# PS_GTR.net
KiCad netlist of a schematic drawn in Altium Designer
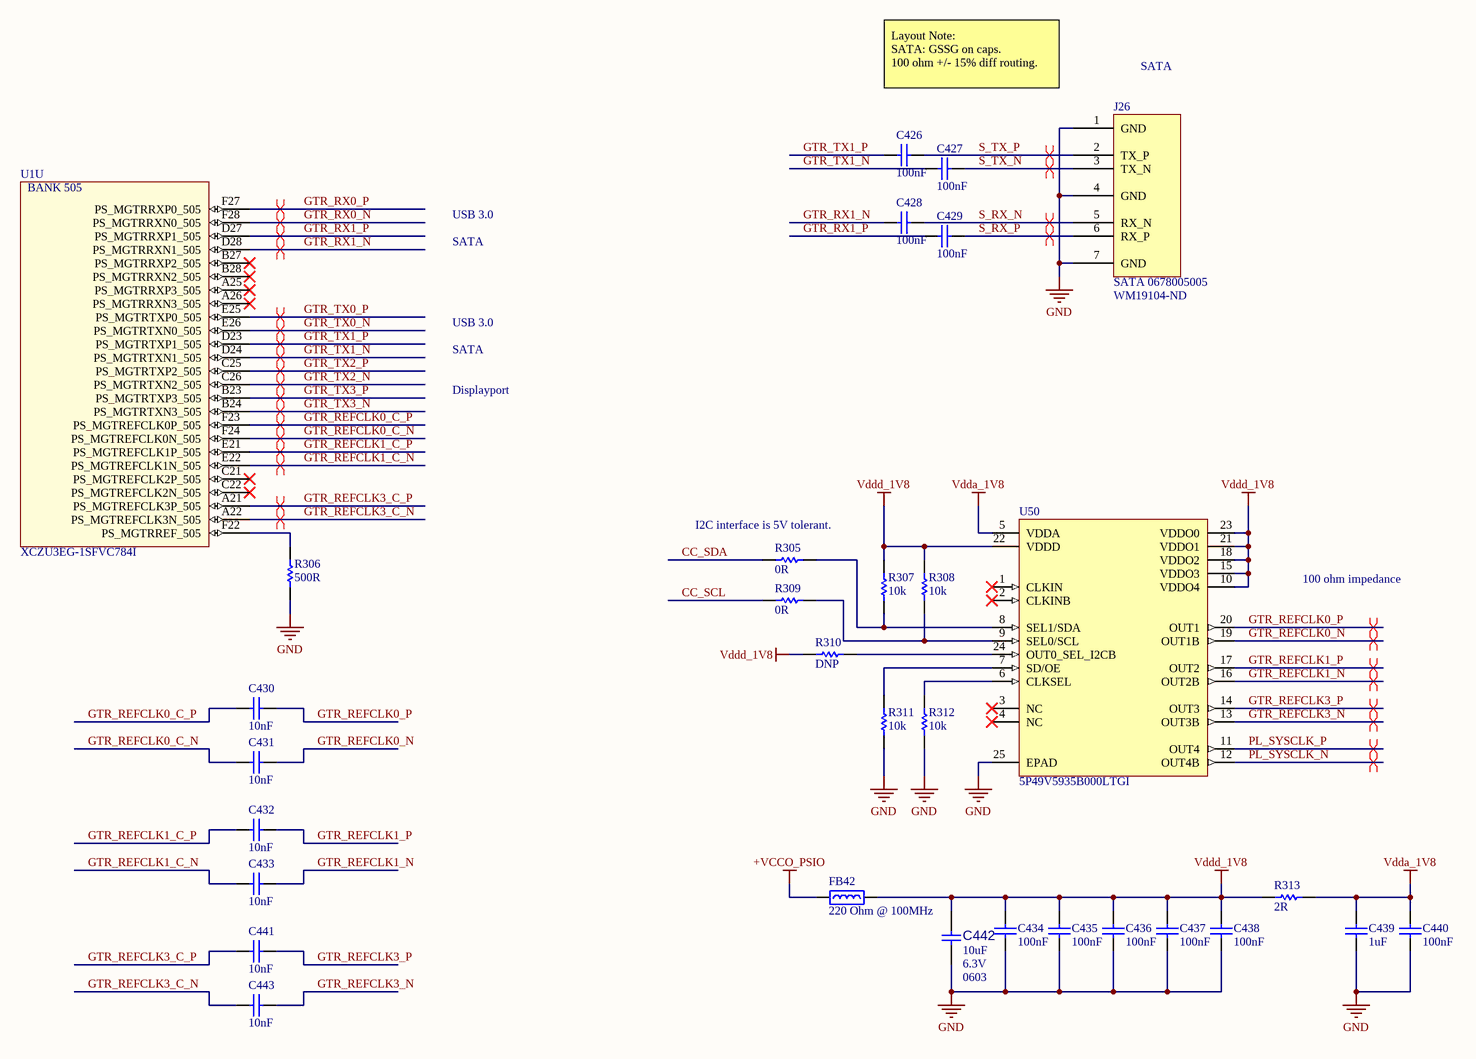
[diagram p0: PS_GTR.SchDoc]

(export (version "E")
  (design (tool "Eeschema 10.0.6"))
  (components
    (comp (ref "C426")
      (value "100nF")
      (footprint "CAPC1005L_0402")
      (description "CAP CER 0.1UF 25V X7R 0402")
      (fields (field (name "VOLTAGE") "25V") (field (name "TOLERANCE") "10%"))
      (libsource (lib "Ultrascale_SchLib") (part "CAPCER0402X7R100N25V_10T"))
    )
    (comp (ref "C427")
      (value "100nF")
      (footprint "CAPC1005L_0402")
      (description "CAP CER 0.1UF 25V X7R 0402")
      (fields (field (name "VOLTAGE") "25V") (field (name "TOLERANCE") "10%"))
      (libsource (lib "Ultrascale_SchLib") (part "CAPCER0402X7R100N25V_10T"))
    )
    (comp (ref "C428")
      (value "100nF")
      (footprint "CAPC1005L_0402")
      (description "CAP CER 0.1UF 25V X7R 0402")
      (fields (field (name "VOLTAGE") "25V") (field (name "TOLERANCE") "10%"))
      (libsource (lib "Ultrascale_SchLib") (part "CAPCER0402X7R100N25V_10T"))
    )
    (comp (ref "C429")
      (value "100nF")
      (footprint "CAPC1005L_0402")
      (description "CAP CER 0.1UF 25V X7R 0402")
      (fields (field (name "VOLTAGE") "25V") (field (name "TOLERANCE") "10%"))
      (libsource (lib "Ultrascale_SchLib") (part "CAPCER0402X7R100N25V_10T"))
    )
    (comp (ref "C430")
      (value "10nF")
      (footprint "CAPC1005L_0402")
      (description "CAP CER 10000PF (10NF) 50V X7R 0402")
      (fields (field (name "VOLTAGE") "50V") (field (name "TOLERANCE") "10%"))
      (libsource (lib "Ultrascale_SchLib") (part "CAPCER0402X7R10N50V_10T"))
    )
    (comp (ref "C431")
      (value "10nF")
      (footprint "CAPC1005L_0402")
      (description "CAP CER 10000PF (10NF) 50V X7R 0402")
      (fields (field (name "VOLTAGE") "50V") (field (name "TOLERANCE") "10%"))
      (libsource (lib "Ultrascale_SchLib") (part "CAPCER0402X7R10N50V_10T"))
    )
    (comp (ref "C432")
      (value "10nF")
      (footprint "CAPC1005L_0402")
      (description "CAP CER 10000PF (10NF) 50V X7R 0402")
      (fields (field (name "VOLTAGE") "50V") (field (name "TOLERANCE") "10%"))
      (libsource (lib "Ultrascale_SchLib") (part "CAPCER0402X7R10N50V_10T"))
    )
    (comp (ref "C433")
      (value "10nF")
      (footprint "CAPC1005L_0402")
      (description "CAP CER 10000PF (10NF) 50V X7R 0402")
      (fields (field (name "VOLTAGE") "50V") (field (name "TOLERANCE") "10%"))
      (libsource (lib "Ultrascale_SchLib") (part "CAPCER0402X7R10N50V_10T"))
    )
    (comp (ref "C434")
      (value "100nF")
      (footprint "CAPC1005L_0402")
      (description "CAP CER 0.1UF 25V X7R 0402")
      (fields (field (name "VOLTAGE") "25V") (field (name "TOLERANCE") "10%"))
      (libsource (lib "Ultrascale_SchLib") (part "CAPCER0402X7R100N25V_10T"))
    )
    (comp (ref "C435")
      (value "100nF")
      (footprint "CAPC1005L_0402")
      (description "CAP CER 0.1UF 25V X7R 0402")
      (fields (field (name "VOLTAGE") "25V") (field (name "TOLERANCE") "10%"))
      (libsource (lib "Ultrascale_SchLib") (part "CAPCER0402X7R100N25V_10T"))
    )
    (comp (ref "C436")
      (value "100nF")
      (footprint "CAPC1005L_0402")
      (description "CAP CER 0.1UF 25V X7R 0402")
      (fields (field (name "VOLTAGE") "25V") (field (name "TOLERANCE") "10%"))
      (libsource (lib "Ultrascale_SchLib") (part "CAPCER0402X7R100N25V_10T"))
    )
    (comp (ref "C437")
      (value "100nF")
      (footprint "CAPC1005L_0402")
      (description "CAP CER 0.1UF 25V X7R 0402")
      (fields (field (name "VOLTAGE") "25V") (field (name "TOLERANCE") "10%"))
      (libsource (lib "Ultrascale_SchLib") (part "CAPCER0402X7R100N25V_10T"))
    )
    (comp (ref "C438")
      (value "100nF")
      (footprint "CAPC1005L_0402")
      (description "CAP CER 0.1UF 25V X7R 0402")
      (fields (field (name "VOLTAGE") "25V") (field (name "TOLERANCE") "10%"))
      (libsource (lib "Ultrascale_SchLib") (part "CAPCER0402X7R100N25V_10T"))
    )
    (comp (ref "C439")
      (value "1uF")
      (footprint "CAPC1005L_0402")
      (description "CAP CER 1UF 16V X5R 0402")
      (fields (field (name "VOLTAGE") "16V") (field (name "TOLERANCE") "20%"))
      (libsource (lib "Ultrascale_SchLib") (part "CAPCER0402X5R1U16V_20T"))
    )
    (comp (ref "C440")
      (value "100nF")
      (footprint "CAPC1005L_0402")
      (description "CAP CER 0.1UF 25V X7R 0402")
      (fields (field (name "VOLTAGE") "25V") (field (name "TOLERANCE") "10%"))
      (libsource (lib "Ultrascale_SchLib") (part "CAPCER0402X7R100N25V_10T"))
    )
    (comp (ref "C441")
      (value "10nF")
      (footprint "CAPC1005L_0402")
      (description "CAP CER 10000PF (10NF) 50V X7R 0402")
      (fields (field (name "VOLTAGE") "50V") (field (name "TOLERANCE") "10%"))
      (libsource (lib "Ultrascale_SchLib") (part "CAPCER0402X7R10N50V_10T"))
    )
    (comp (ref "C442")
      (value "10uF")
      (footprint "Ultrascale_PcbLib:CAP_C_0603")
      (description "Capacitor")
      (fields
        (field (name "VOLTAGE") "6.3V")
        (field (name "PACKAGE") "0603")
        (field (name "TOLERANCE") "20%")
        (field (name "Comment") "Capacitor NP")
      )
      (libsource (lib "Ultrascale_SchLib") (part "Capacitor NP"))
    )
    (comp (ref "C443")
      (value "10nF")
      (footprint "CAPC1005L_0402")
      (description "CAP CER 10000PF (10NF) 50V X7R 0402")
      (fields (field (name "VOLTAGE") "50V") (field (name "TOLERANCE") "10%"))
      (libsource (lib "Ultrascale_SchLib") (part "CAPCER0402X7R10N50V_10T"))
    )
    (comp (ref "FB42")
      (value "BEAD0603_220_2A5_40M")
      (footprint "INDC1608N_0603")
      (description "FERRITE BEAD 220 OHM 0603 1LN")
      (fields (field (name "IMPEDANCE @ FREQUENCY") "220 Ohm @ 100MHz"))
      (libsource (lib "Ultrascale_SchLib") (part "BEAD0603_220_2A5_40M"))
    )
    (comp (ref "J26")
      (value "SATA 0678005005")
      (footprint "SATA HEADER")
      (description "CONN HEADER 7POS VERT SMD 15GOLD")
      (fields
        (field (name "DIGI-KEY PART NUMBER") "WM19104-ND")
        (field (name "MANUFACTURER") "Molex, LLC")
        (field (name "SUPPLIER PART NUMBER 1") "WM19104-ND")
      )
      (libsource (lib "Ultrascale_SchLib") (part "SATA 0678005005"))
    )
    (comp (ref "R305")
      (value "0R")
      (footprint "RESC1005L_0402")
      (description "RES SMD 0 OHM JUMPER 1/10W 0402")
      (fields (field (name "POWER") "1/10W") (field (name "Comment") "RES0402_0R_0W1"))
      (libsource (lib "Ultrascale_SchLib") (part "RES0402_0R_0W1"))
    )
    (comp (ref "R306")
      (value "500R")
      (footprint "RESC1005L_0402")
      (description "RES SMD 500 OHM 0.1% 1/20W 0402")
      (fields (field (name "POWER") "1/10W") (field (name "TOLERANCE") "0.1%"))
      (libsource (lib "Ultrascale_SchLib") (part "RES0402_500R_0W05_01T"))
    )
    (comp (ref "R307")
      (value "10k")
      (footprint "RESC1005L_0402")
      (description "RES SMD 10K OHM 0.5% 1/16W 0402")
      (fields (field (name "POWER") "1/16W") (field (name "TOLERANCE") "0.5%"))
      (libsource (lib "Ultrascale_SchLib") (part "RES0402_10K_0W1_05T"))
    )
    (comp (ref "R308")
      (value "10k")
      (footprint "RESC1005L_0402")
      (description "RES SMD 10K OHM 0.5% 1/16W 0402")
      (fields (field (name "POWER") "1/16W") (field (name "TOLERANCE") "0.5%"))
      (libsource (lib "Ultrascale_SchLib") (part "RES0402_10K_0W1_05T"))
    )
    (comp (ref "R309")
      (value "0R")
      (footprint "RESC1005L_0402")
      (description "RES SMD 0 OHM JUMPER 1/10W 0402")
      (fields (field (name "POWER") "1/10W") (field (name "Comment") "RES0402_0R_0W1"))
      (libsource (lib "Ultrascale_SchLib") (part "RES0402_0R_0W1"))
    )
    (comp (ref "R310")
      (value "DNP")
      (footprint "RESC1005L_0402")
      (description "RES SMD 0402 Footprint")
      (fields (field (name "Comment") "RES0402"))
      (libsource (lib "Ultrascale_SchLib") (part "RES0402"))
    )
    (comp (ref "R311")
      (value "10k")
      (footprint "RESC1005L_0402")
      (description "RES SMD 10K OHM 0.5% 1/16W 0402")
      (fields (field (name "POWER") "1/16W") (field (name "TOLERANCE") "0.5%"))
      (libsource (lib "Ultrascale_SchLib") (part "RES0402_10K_0W1_05T"))
    )
    (comp (ref "R312")
      (value "10k")
      (footprint "RESC1005L_0402")
      (description "RES SMD 10K OHM 0.5% 1/16W 0402")
      (fields (field (name "POWER") "1/16W") (field (name "TOLERANCE") "0.5%"))
      (libsource (lib "Ultrascale_SchLib") (part "RES0402_10K_0W1_05T"))
    )
    (comp (ref "R313")
      (value "2R")
      (footprint "RESC1005L_0402")
      (description "RES SMD 2 OHM 1% 1/16W 0402")
      (fields (field (name "POWER") "1/10W") (field (name "TOLERANCE") "1%"))
      (libsource (lib "Ultrascale_SchLib") (part "RES0402_2R_0W1_1T"))
    )
    (comp (ref "U1")
      (value "XCZU3EG-1SFVC784I")
      (footprint "BGA784x28")
      (description "IC FPGA 252 I/O 784FCBGA - XILINX ZYNQ ULTRASCALE+")
      (libsource (lib "Ultrascale_SchLib") (part "XCZU3EG-1SFVC784I"))
    )
    (comp (ref "U50")
      (value "5P49V5935B000LTGI")
      (footprint "LGA24_5P49V5935B000LTGI")
      (description "IC CLOCK GENERATOR 24LGA")
      (libsource (lib "Ultrascale_SchLib") (part "5P49V5935B000LTGI"))
    )
  )
  (nets
    (net (code "1") (name "+VCCO_PSIO") (class "Default")
      (node (ref "FB42") (pin "1") (pinfunction "1_1") (pintype "passive"))
    )
    (net (code "2") (name "/CC_SCL") (class "Default")
      (node (ref "R309") (pin "1") (pinfunction "1_1") (pintype "passive"))
    )
    (net (code "3") (name "/CC_SDA") (class "Default")
      (node (ref "R305") (pin "1") (pinfunction "1_1") (pintype "passive"))
    )
    (net (code "4") (name "/GTR_REFCLK0_C_N") (class "Default")
      (node (ref "C431") (pin "1") (pinfunction "1_1") (pintype "passive"))
      (node (ref "U1") (pin "F24") (pinfunction "PS_MGTREFCLK0N_505_F24") (pintype "bidirectional"))
    )
    (net (code "5") (name "/GTR_REFCLK0_C_P") (class "Default")
      (node (ref "C430") (pin "1") (pinfunction "1_1") (pintype "passive"))
      (node (ref "U1") (pin "F23") (pinfunction "PS_MGTREFCLK0P_505_F23") (pintype "bidirectional"))
    )
    (net (code "6") (name "/GTR_REFCLK0_N") (class "Default")
      (node (ref "C431") (pin "2") (pinfunction "2_2") (pintype "passive"))
      (node (ref "U50") (pin "19") (pinfunction "OUT1B_19") (pintype "output"))
    )
    (net (code "7") (name "/GTR_REFCLK0_P") (class "Default")
      (node (ref "C430") (pin "2") (pinfunction "2_2") (pintype "passive"))
      (node (ref "U50") (pin "20") (pinfunction "OUT1_20") (pintype "output"))
    )
    (net (code "8") (name "/GTR_REFCLK1_C_N") (class "Default")
      (node (ref "C433") (pin "1") (pinfunction "1_1") (pintype "passive"))
      (node (ref "U1") (pin "E22") (pinfunction "PS_MGTREFCLK1N_505_E22") (pintype "bidirectional"))
    )
    (net (code "9") (name "/GTR_REFCLK1_C_P") (class "Default")
      (node (ref "C432") (pin "1") (pinfunction "1_1") (pintype "passive"))
      (node (ref "U1") (pin "E21") (pinfunction "PS_MGTREFCLK1P_505_E21") (pintype "bidirectional"))
    )
    (net (code "10") (name "/GTR_REFCLK1_N") (class "Default")
      (node (ref "C433") (pin "2") (pinfunction "2_2") (pintype "passive"))
      (node (ref "U50") (pin "16") (pinfunction "OUT2B_16") (pintype "output"))
    )
    (net (code "11") (name "/GTR_REFCLK1_P") (class "Default")
      (node (ref "C432") (pin "2") (pinfunction "2_2") (pintype "passive"))
      (node (ref "U50") (pin "17") (pinfunction "OUT2_17") (pintype "output"))
    )
    (net (code "12") (name "/GTR_REFCLK3_C_N") (class "Default")
      (node (ref "C443") (pin "1") (pinfunction "1_1") (pintype "passive"))
      (node (ref "U1") (pin "A22") (pinfunction "PS_MGTREFCLK3N_505_A22") (pintype "bidirectional"))
    )
    (net (code "13") (name "/GTR_REFCLK3_C_P") (class "Default")
      (node (ref "C441") (pin "1") (pinfunction "1_1") (pintype "passive"))
      (node (ref "U1") (pin "A21") (pinfunction "PS_MGTREFCLK3P_505_A21") (pintype "bidirectional"))
    )
    (net (code "14") (name "/GTR_REFCLK3_N") (class "Default")
      (node (ref "C443") (pin "2") (pinfunction "2_2") (pintype "passive"))
      (node (ref "U50") (pin "13") (pinfunction "OUT3B_13") (pintype "output"))
    )
    (net (code "15") (name "/GTR_REFCLK3_P") (class "Default")
      (node (ref "C441") (pin "2") (pinfunction "2_2") (pintype "passive"))
      (node (ref "U50") (pin "14") (pinfunction "OUT3_14") (pintype "output"))
    )
    (net (code "16") (name "/GTR_RX0_N") (class "Default")
      (node (ref "U1") (pin "F28") (pinfunction "PS_MGTRRXN0_505_F28") (pintype "bidirectional"))
    )
    (net (code "17") (name "/GTR_RX0_P") (class "Default")
      (node (ref "U1") (pin "F27") (pinfunction "PS_MGTRRXP0_505_F27") (pintype "bidirectional"))
    )
    (net (code "18") (name "/GTR_RX1_N") (class "Default")
      (node (ref "C428") (pin "1") (pinfunction "1_1") (pintype "passive"))
      (node (ref "U1") (pin "D28") (pinfunction "PS_MGTRRXN1_505_D28") (pintype "bidirectional"))
    )
    (net (code "19") (name "/GTR_RX1_P") (class "Default")
      (node (ref "C429") (pin "1") (pinfunction "1_1") (pintype "passive"))
      (node (ref "U1") (pin "D27") (pinfunction "PS_MGTRRXP1_505_D27") (pintype "bidirectional"))
    )
    (net (code "20") (name "/GTR_TX0_N") (class "Default")
      (node (ref "U1") (pin "E26") (pinfunction "PS_MGTRTXN0_505_E26") (pintype "bidirectional"))
    )
    (net (code "21") (name "/GTR_TX0_P") (class "Default")
      (node (ref "U1") (pin "E25") (pinfunction "PS_MGTRTXP0_505_E25") (pintype "bidirectional"))
    )
    (net (code "22") (name "/GTR_TX1_N") (class "Default")
      (node (ref "C427") (pin "1") (pinfunction "1_1") (pintype "passive"))
      (node (ref "U1") (pin "D24") (pinfunction "PS_MGTRTXN1_505_D24") (pintype "bidirectional"))
    )
    (net (code "23") (name "/GTR_TX1_P") (class "Default")
      (node (ref "C426") (pin "1") (pinfunction "1_1") (pintype "passive"))
      (node (ref "U1") (pin "D23") (pinfunction "PS_MGTRTXP1_505_D23") (pintype "bidirectional"))
    )
    (net (code "24") (name "/GTR_TX2_N") (class "Default")
      (node (ref "U1") (pin "C26") (pinfunction "PS_MGTRTXN2_505_C26") (pintype "bidirectional"))
    )
    (net (code "25") (name "/GTR_TX2_P") (class "Default")
      (node (ref "U1") (pin "C25") (pinfunction "PS_MGTRTXP2_505_C25") (pintype "bidirectional"))
    )
    (net (code "26") (name "/GTR_TX3_N") (class "Default")
      (node (ref "U1") (pin "B24") (pinfunction "PS_MGTRTXN3_505_B24") (pintype "bidirectional"))
    )
    (net (code "27") (name "/GTR_TX3_P") (class "Default")
      (node (ref "U1") (pin "B23") (pinfunction "PS_MGTRTXP3_505_B23") (pintype "bidirectional"))
    )
    (net (code "28") (name "/PL_SYSCLK_N") (class "Default")
      (node (ref "U50") (pin "12") (pinfunction "OUT4B_12") (pintype "output"))
    )
    (net (code "29") (name "/PL_SYSCLK_P") (class "Default")
      (node (ref "U50") (pin "11") (pinfunction "OUT4_11") (pintype "output"))
    )
    (net (code "30") (name "/S_RX_N") (class "Default")
      (node (ref "C428") (pin "2") (pinfunction "2_2") (pintype "passive"))
      (node (ref "J26") (pin "5") (pinfunction "RX_N_5") (pintype "power_in"))
    )
    (net (code "31") (name "/S_RX_P") (class "Default")
      (node (ref "C429") (pin "2") (pinfunction "2_2") (pintype "passive"))
      (node (ref "J26") (pin "6") (pinfunction "RX_P_6") (pintype "power_in"))
    )
    (net (code "32") (name "/S_TX_N") (class "Default")
      (node (ref "C427") (pin "2") (pinfunction "2_2") (pintype "passive"))
      (node (ref "J26") (pin "3") (pinfunction "TX_N_3") (pintype "power_in"))
    )
    (net (code "33") (name "/S_TX_P") (class "Default")
      (node (ref "C426") (pin "2") (pinfunction "2_2") (pintype "passive"))
      (node (ref "J26") (pin "2") (pinfunction "TX_P_2") (pintype "power_in"))
    )
    (net (code "34") (name "GND") (class "Default")
      (node (ref "C434") (pin "1") (pinfunction "1_1") (pintype "passive"))
      (node (ref "C435") (pin "1") (pinfunction "1_1") (pintype "passive"))
      (node (ref "C436") (pin "1") (pinfunction "1_1") (pintype "passive"))
      (node (ref "C437") (pin "1") (pinfunction "1_1") (pintype "passive"))
      (node (ref "C438") (pin "1") (pinfunction "1_1") (pintype "passive"))
      (node (ref "C439") (pin "1") (pinfunction "1_1") (pintype "passive"))
      (node (ref "C440") (pin "1") (pinfunction "1_1") (pintype "passive"))
      (node (ref "C442") (pin "1") (pinfunction "1_1") (pintype "passive"))
      (node (ref "J26") (pin "1") (pinfunction "GND_1") (pintype "power_in"))
      (node (ref "J26") (pin "4") (pinfunction "GND_4") (pintype "power_in"))
      (node (ref "J26") (pin "7") (pinfunction "GND_7") (pintype "power_in"))
      (node (ref "R306") (pin "1") (pinfunction "1_1") (pintype "passive"))
      (node (ref "R311") (pin "1") (pinfunction "1_1") (pintype "passive"))
      (node (ref "R312") (pin "1") (pinfunction "1_1") (pintype "passive"))
      (node (ref "U50") (pin "25") (pinfunction "EPAD_25") (pintype "passive"))
    )
    (net (code "35") (name "Net-(U1U-PS_MGTRREF_505)") (class "Default")
      (node (ref "R306") (pin "2") (pinfunction "2_2") (pintype "passive"))
      (node (ref "U1") (pin "F22") (pinfunction "PS_MGTRREF_505_F22") (pintype "bidirectional"))
    )
    (net (code "36") (name "Net-(U50-CLKSEL)") (class "Default")
      (node (ref "R312") (pin "2") (pinfunction "2_2") (pintype "passive"))
      (node (ref "U50") (pin "6") (pinfunction "CLKSEL_6") (pintype "input"))
    )
    (net (code "37") (name "Net-(U50-OUT0_SEL_I2CB)") (class "Default")
      (node (ref "R310") (pin "2") (pinfunction "2_2") (pintype "passive"))
      (node (ref "U50") (pin "24") (pinfunction "OUT0_SEL_I2CB_24") (pintype "input"))
    )
    (net (code "38") (name "Net-(U50-SD{slash}OE)") (class "Default")
      (node (ref "R311") (pin "2") (pinfunction "2_2") (pintype "passive"))
      (node (ref "U50") (pin "7") (pinfunction "SD/OE_7") (pintype "input"))
    )
    (net (code "39") (name "Net-(U50-SEL0{slash}SCL)") (class "Default")
      (node (ref "R308") (pin "1") (pinfunction "1_1") (pintype "passive"))
      (node (ref "R309") (pin "2") (pinfunction "2_2") (pintype "passive"))
      (node (ref "U50") (pin "9") (pinfunction "SEL0/SCL_9") (pintype "input"))
    )
    (net (code "40") (name "Net-(U50-SEL1{slash}SDA)") (class "Default")
      (node (ref "R305") (pin "2") (pinfunction "2_2") (pintype "passive"))
      (node (ref "R307") (pin "1") (pinfunction "1_1") (pintype "passive"))
      (node (ref "U50") (pin "8") (pinfunction "SEL1/SDA_8") (pintype "input"))
    )
    (net (code "41") (name "Vdda_1V8") (class "Default")
      (node (ref "C439") (pin "2") (pinfunction "2_2") (pintype "passive"))
      (node (ref "C440") (pin "2") (pinfunction "2_2") (pintype "passive"))
      (node (ref "R313") (pin "2") (pinfunction "2_2") (pintype "passive"))
      (node (ref "U50") (pin "5") (pinfunction "VDDA_5") (pintype "passive"))
    )
    (net (code "42") (name "Vddd_1V8") (class "Default")
      (node (ref "C434") (pin "2") (pinfunction "2_2") (pintype "passive"))
      (node (ref "C435") (pin "2") (pinfunction "2_2") (pintype "passive"))
      (node (ref "C436") (pin "2") (pinfunction "2_2") (pintype "passive"))
      (node (ref "C437") (pin "2") (pinfunction "2_2") (pintype "passive"))
      (node (ref "C438") (pin "2") (pinfunction "2_2") (pintype "passive"))
      (node (ref "C442") (pin "2") (pinfunction "2_2") (pintype "passive"))
      (node (ref "FB42") (pin "2") (pinfunction "2_2") (pintype "passive"))
      (node (ref "R307") (pin "2") (pinfunction "2_2") (pintype "passive"))
      (node (ref "R308") (pin "2") (pinfunction "2_2") (pintype "passive"))
      (node (ref "R310") (pin "1") (pinfunction "1_1") (pintype "passive"))
      (node (ref "R313") (pin "1") (pinfunction "1_1") (pintype "passive"))
      (node (ref "U50") (pin "10") (pinfunction "VDDO4_10") (pintype "passive"))
      (node (ref "U50") (pin "15") (pinfunction "VDDO3_15") (pintype "passive"))
      (node (ref "U50") (pin "18") (pinfunction "VDDO2_18") (pintype "passive"))
      (node (ref "U50") (pin "21") (pinfunction "VDDO1_21") (pintype "passive"))
      (node (ref "U50") (pin "22") (pinfunction "VDDD_22") (pintype "passive"))
      (node (ref "U50") (pin "23") (pinfunction "VDDO0_23") (pintype "passive"))
    )
    (net (code "43") (name "unconnected-(U1U-PS_MGTREFCLK2N_505-PadC22)") (class "Default")
      (node (ref "U1") (pin "C22") (pinfunction "PS_MGTREFCLK2N_505_C22") (pintype "bidirectional+no_connect"))
    )
    (net (code "44") (name "unconnected-(U1U-PS_MGTREFCLK2P_505-PadC21)") (class "Default")
      (node (ref "U1") (pin "C21") (pinfunction "PS_MGTREFCLK2P_505_C21") (pintype "bidirectional+no_connect"))
    )
    (net (code "45") (name "unconnected-(U1U-PS_MGTRRXN2_505-PadB28)") (class "Default")
      (node (ref "U1") (pin "B28") (pinfunction "PS_MGTRRXN2_505_B28") (pintype "bidirectional+no_connect"))
    )
    (net (code "46") (name "unconnected-(U1U-PS_MGTRRXN3_505-PadA26)") (class "Default")
      (node (ref "U1") (pin "A26") (pinfunction "PS_MGTRRXN3_505_A26") (pintype "bidirectional+no_connect"))
    )
    (net (code "47") (name "unconnected-(U1U-PS_MGTRRXP2_505-PadB27)") (class "Default")
      (node (ref "U1") (pin "B27") (pinfunction "PS_MGTRRXP2_505_B27") (pintype "bidirectional+no_connect"))
    )
    (net (code "48") (name "unconnected-(U1U-PS_MGTRRXP3_505-PadA25)") (class "Default")
      (node (ref "U1") (pin "A25") (pinfunction "PS_MGTRRXP3_505_A25") (pintype "bidirectional+no_connect"))
    )
    (net (code "49") (name "unconnected-(U50-CLKIN-Pad1)") (class "Default")
      (node (ref "U50") (pin "1") (pinfunction "CLKIN_1") (pintype "input+no_connect"))
    )
    (net (code "50") (name "unconnected-(U50-CLKINB-Pad2)") (class "Default")
      (node (ref "U50") (pin "2") (pinfunction "CLKINB_2") (pintype "input+no_connect"))
    )
    (net (code "51") (name "unconnected-(U50-NC-Pad3)") (class "Default")
      (node (ref "U50") (pin "3") (pinfunction "NC_3") (pintype "passive+no_connect"))
    )
    (net (code "52") (name "unconnected-(U50-NC-Pad4)") (class "Default")
      (node (ref "U50") (pin "4") (pinfunction "NC_4") (pintype "passive+no_connect"))
    )
  )
)
